# ArduinoNano.net
KiCad netlist of a schematic drawn in Altium Designer
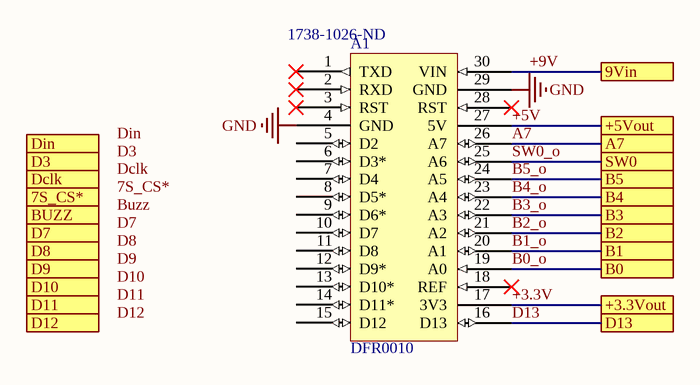
[diagram p0: ArduinoNano.SchDoc]

(export (version "E")
  (design (tool "Eeschema 10.0.6"))
  (components
    (comp (ref "A1")
      (value "DFR0010")
      (footprint "ArduinoNano")
      (description "DFRDUINO NANO V3.1 (ARDUINO NANO")
      (fields (field (name "SUPPLIER PART NUMBER 1") "1738-1026-ND"))
      (libsource (lib "ServoInterface") (part "ArduinoNano"))
    )
  )
  (nets
    (net (code "1") (name "/+3.3V") (class "Default")
      (node (ref "A1") (pin "17") (pinfunction "3V3_17") (pintype "power_in"))
    )
    (net (code "2") (name "/+5V") (class "Default")
      (node (ref "A1") (pin "27") (pinfunction "5V_27") (pintype "power_in"))
    )
    (net (code "3") (name "/+9V") (class "Default")
      (node (ref "A1") (pin "30") (pinfunction "VIN_30") (pintype "input"))
    )
    (net (code "5") (name "/A7") (class "Default")
      (node (ref "A1") (pin "26") (pinfunction "A7_26") (pintype "bidirectional"))
    )
    (net (code "6") (name "/B0_o") (class "Default")
      (node (ref "A1") (pin "19") (pinfunction "A0_19") (pintype "input"))
    )
    (net (code "7") (name "/B1_o") (class "Default")
      (node (ref "A1") (pin "20") (pinfunction "A1_20") (pintype "bidirectional"))
    )
    (net (code "8") (name "/B2_o") (class "Default")
      (node (ref "A1") (pin "21") (pinfunction "A2_21") (pintype "bidirectional"))
    )
    (net (code "9") (name "/B3_o") (class "Default")
      (node (ref "A1") (pin "22") (pinfunction "A3_22") (pintype "bidirectional"))
    )
    (net (code "10") (name "/B4_o") (class "Default")
      (node (ref "A1") (pin "23") (pinfunction "A4_23") (pintype "bidirectional"))
    )
    (net (code "11") (name "/B5_o") (class "Default")
      (node (ref "A1") (pin "24") (pinfunction "A5_24") (pintype "bidirectional"))
    )
    (net (code "21") (name "/D13") (class "Default")
      (node (ref "A1") (pin "16") (pinfunction "D13_16") (pintype "bidirectional"))
    )
    (net (code "24") (name "/SW0_o") (class "Default")
      (node (ref "A1") (pin "25") (pinfunction "A6_25") (pintype "bidirectional"))
    )
    (net (code "25") (name "GND") (class "Default")
      (node (ref "A1") (pin "29") (pinfunction "GND_29") (pintype "passive"))
      (node (ref "A1") (pin "4") (pinfunction "GND_4") (pintype "passive"))
    )
    (net (code "26") (name "unconnected-(A1-D2-Pad5)") (class "Default")
      (node (ref "A1") (pin "5") (pinfunction "D2_5") (pintype "bidirectional"))
    )
    (net (code "27") (name "unconnected-(A1-D3*-Pad6)") (class "Default")
      (node (ref "A1") (pin "6") (pinfunction "D3*_6") (pintype "bidirectional"))
    )
    (net (code "28") (name "unconnected-(A1-D4-Pad7)") (class "Default")
      (node (ref "A1") (pin "7") (pinfunction "D4_7") (pintype "bidirectional"))
    )
    (net (code "29") (name "unconnected-(A1-D5*-Pad8)") (class "Default")
      (node (ref "A1") (pin "8") (pinfunction "D5*_8") (pintype "bidirectional"))
    )
    (net (code "30") (name "unconnected-(A1-D6*-Pad9)") (class "Default")
      (node (ref "A1") (pin "9") (pinfunction "D6*_9") (pintype "bidirectional"))
    )
    (net (code "31") (name "unconnected-(A1-D7-Pad10)") (class "Default")
      (node (ref "A1") (pin "10") (pinfunction "D7_10") (pintype "bidirectional"))
    )
    (net (code "32") (name "unconnected-(A1-D8-Pad11)") (class "Default")
      (node (ref "A1") (pin "11") (pinfunction "D8_11") (pintype "bidirectional"))
    )
    (net (code "33") (name "unconnected-(A1-D9*-Pad12)") (class "Default")
      (node (ref "A1") (pin "12") (pinfunction "D9*_12") (pintype "bidirectional"))
    )
    (net (code "34") (name "unconnected-(A1-D10*-Pad13)") (class "Default")
      (node (ref "A1") (pin "13") (pinfunction "D10*_13") (pintype "bidirectional"))
    )
    (net (code "35") (name "unconnected-(A1-D11*-Pad14)") (class "Default")
      (node (ref "A1") (pin "14") (pinfunction "D11*_14") (pintype "bidirectional"))
    )
    (net (code "36") (name "unconnected-(A1-D12-Pad15)") (class "Default")
      (node (ref "A1") (pin "15") (pinfunction "D12_15") (pintype "bidirectional"))
    )
    (net (code "37") (name "unconnected-(A1-REF-Pad18)") (class "Default")
      (node (ref "A1") (pin "18") (pinfunction "REF_18") (pintype "input+no_connect"))
    )
    (net (code "38") (name "unconnected-(A1-RST-Pad3)") (class "Default")
      (node (ref "A1") (pin "3") (pinfunction "RST_3") (pintype "input+no_connect"))
    )
    (net (code "39") (name "unconnected-(A1-RST-Pad28)") (class "Default")
      (node (ref "A1") (pin "28") (pinfunction "RST_28") (pintype "input+no_connect"))
    )
    (net (code "40") (name "unconnected-(A1-RXD-Pad2)") (class "Default")
      (node (ref "A1") (pin "2") (pinfunction "RXD_2") (pintype "input+no_connect"))
    )
    (net (code "41") (name "unconnected-(A1-TXD-Pad1)") (class "Default")
      (node (ref "A1") (pin "1") (pinfunction "TXD_1") (pintype "output+no_connect"))
    )
  )
)
